# CircuitDiagram.net
KiCad netlist of a schematic drawn in EAGLE
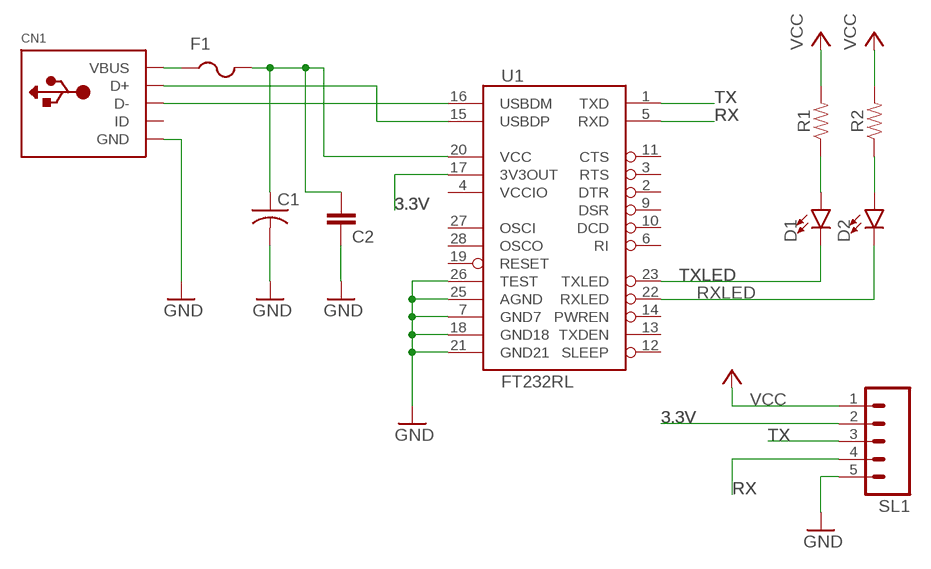
[diagram p0: schematic, sheet 1]

(export (version "E")
  (design (tool "Eeschema 10.0.6"))
  (components
    (comp (ref "C1")
      (value "C-USC1206")
      (footprint "eagle-import:C1206")
      (libsource (lib "eagle-import") (part "C-USC1206"))
    )
    (comp (ref "C2")
      (value "1.0uF")
      (footprint "eagle-import:1206")
      (libsource (lib "eagle-import") (part "1.0UF-1206-50V-10%"))
    )
    (comp (ref "CN1")
      (value "USBMINIB")
      (footprint "eagle-import:USB-MINIB")
      (libsource (lib "eagle-import") (part "USBMINIB"))
    )
    (comp (ref "D1")
      (value "LED1206")
      (footprint "eagle-import:LED-1206")
      (libsource (lib "eagle-import") (part "LED1206"))
    )
    (comp (ref "D2")
      (value "LED1206")
      (footprint "eagle-import:LED-1206")
      (libsource (lib "eagle-import") (part "LED1206"))
    )
    (comp (ref "F1")
      (value "PTCFUSE-1206")
      (footprint "eagle-import:R1206")
      (libsource (lib "eagle-import") (part "PTCFUSE-1206"))
    )
    (comp (ref "R1")
      (value "RESISTOR1206")
      (footprint "eagle-import:1206")
      (libsource (lib "eagle-import") (part "RESISTOR1206"))
    )
    (comp (ref "R2")
      (value "RESISTOR1206")
      (footprint "eagle-import:1206")
      (libsource (lib "eagle-import") (part "RESISTOR1206"))
    )
    (comp (ref "SL1")
      (value "M05")
      (footprint "eagle-import:05P")
      (libsource (lib "eagle-import") (part "M05"))
    )
    (comp (ref "U1")
      (value "FT232RL")
      (footprint "eagle-import:SSOP28DB")
      (libsource (lib "eagle-import") (part "FT232RLSSOP"))
    )
  )
  (nets
    (net (code "1") (name "/3.3V") (class "Default")
      (node (ref "SL1") (pin "2") (pinfunction "2_2") (pintype "passive"))
      (node (ref "U1") (pin "17") (pinfunction "3V3OUT_17") (pintype "output"))
    )
    (net (code "2") (name "/RX") (class "Default")
      (node (ref "SL1") (pin "4") (pinfunction "4_4") (pintype "passive"))
      (node (ref "U1") (pin "5") (pinfunction "RXD_5") (pintype "input"))
    )
    (net (code "3") (name "/RXLED") (class "Default")
      (node (ref "D2") (pin "C") (pinfunction "C_C") (pintype "passive"))
      (node (ref "U1") (pin "22") (pinfunction "RXLED_22") (pintype "input"))
    )
    (net (code "4") (name "/TX") (class "Default")
      (node (ref "SL1") (pin "3") (pinfunction "3_3") (pintype "passive"))
      (node (ref "U1") (pin "1") (pinfunction "TXD_1") (pintype "output"))
    )
    (net (code "5") (name "/TXLED") (class "Default")
      (node (ref "D1") (pin "C") (pinfunction "C_C") (pintype "passive"))
      (node (ref "U1") (pin "23") (pinfunction "TXLED_23") (pintype "input"))
    )
    (net (code "6") (name "/VCCIO") (class "Default")
      (node (ref "U1") (pin "4") (pinfunction "VCCIO_4") (pintype "power_in"))
    )
    (net (code "7") (name "GND") (class "Default")
      (node (ref "C1") (pin "2") (pinfunction "2_2") (pintype "passive"))
      (node (ref "C2") (pin "2") (pinfunction "2_2") (pintype "passive"))
      (node (ref "CN1") (pin "GND") (pinfunction "GND_GND") (pintype "power_in"))
      (node (ref "SL1") (pin "5") (pinfunction "5_5") (pintype "passive"))
      (node (ref "U1") (pin "18") (pinfunction "GND18_18") (pintype "power_in"))
      (node (ref "U1") (pin "21") (pinfunction "GND21_21") (pintype "power_in"))
      (node (ref "U1") (pin "25") (pinfunction "AGND_25") (pintype "power_in"))
      (node (ref "U1") (pin "26") (pinfunction "TEST_26") (pintype "input"))
      (node (ref "U1") (pin "7") (pinfunction "GND7_7") (pintype "power_in"))
    )
    (net (code "8") (name "Net-(CN1-PadVBUS)") (class "Default")
      (node (ref "CN1") (pin "VBUS") (pinfunction "VBUS_VBUS") (pintype "power_in"))
      (node (ref "F1") (pin "1") (pinfunction "1_1") (pintype "passive"))
    )
    (net (code "9") (name "Net-(D1-PadA)") (class "Default")
      (node (ref "D1") (pin "A") (pinfunction "A_A") (pintype "passive"))
      (node (ref "R1") (pin "1") (pinfunction "1_1") (pintype "passive"))
    )
    (net (code "10") (name "Net-(D2-PadA)") (class "Default")
      (node (ref "D2") (pin "A") (pinfunction "A_A") (pintype "passive"))
      (node (ref "R2") (pin "1") (pinfunction "1_1") (pintype "passive"))
    )
    (net (code "11") (name "Net-(U1-USBDM)") (class "Default")
      (node (ref "CN1") (pin "D-") (pinfunction "D-_D-") (pintype "bidirectional"))
      (node (ref "U1") (pin "16") (pinfunction "USBDM_16") (pintype "bidirectional"))
    )
    (net (code "12") (name "Net-(U1-USBDP)") (class "Default")
      (node (ref "CN1") (pin "D+") (pinfunction "D+_D+") (pintype "bidirectional"))
      (node (ref "U1") (pin "15") (pinfunction "USBDP_15") (pintype "bidirectional"))
    )
    (net (code "13") (name "Net-(U1-VCC)") (class "Default")
      (node (ref "C1") (pin "1") (pinfunction "1_1") (pintype "passive"))
      (node (ref "C2") (pin "1") (pinfunction "1_1") (pintype "passive"))
      (node (ref "F1") (pin "2") (pinfunction "2_2") (pintype "passive"))
      (node (ref "U1") (pin "20") (pinfunction "VCC_20") (pintype "power_in"))
    )
    (net (code "14") (name "VCC") (class "Default")
      (node (ref "R1") (pin "2") (pinfunction "2_2") (pintype "passive"))
      (node (ref "R2") (pin "2") (pinfunction "2_2") (pintype "passive"))
      (node (ref "SL1") (pin "1") (pinfunction "1_1") (pintype "passive"))
    )
    (net (code "15") (name "unconnected-(CN1-PadID)") (class "Default")
      (node (ref "CN1") (pin "ID") (pinfunction "ID_ID") (pintype "bidirectional"))
    )
    (net (code "16") (name "unconnected-(U1-CTS-Pad11)") (class "Default")
      (node (ref "U1") (pin "11") (pinfunction "CTS_11") (pintype "input"))
    )
    (net (code "17") (name "unconnected-(U1-DCD-Pad10)") (class "Default")
      (node (ref "U1") (pin "10") (pinfunction "DCD_10") (pintype "input"))
    )
    (net (code "18") (name "unconnected-(U1-DSR-Pad9)") (class "Default")
      (node (ref "U1") (pin "9") (pinfunction "DSR_9") (pintype "input"))
    )
    (net (code "19") (name "unconnected-(U1-DTR-Pad2)") (class "Default")
      (node (ref "U1") (pin "2") (pinfunction "DTR_2") (pintype "output"))
    )
    (net (code "20") (name "unconnected-(U1-OSCI-Pad27)") (class "Default")
      (node (ref "U1") (pin "27") (pinfunction "OSCI_27") (pintype "input"))
    )
    (net (code "21") (name "unconnected-(U1-OSCO-Pad28)") (class "Default")
      (node (ref "U1") (pin "28") (pinfunction "OSCO_28") (pintype "output"))
    )
    (net (code "22") (name "unconnected-(U1-PWREN-Pad14)") (class "Default")
      (node (ref "U1") (pin "14") (pinfunction "PWREN_14") (pintype "input"))
    )
    (net (code "23") (name "unconnected-(U1-RESET-Pad19)") (class "Default")
      (node (ref "U1") (pin "19") (pinfunction "RESET_19") (pintype "input"))
    )
    (net (code "24") (name "unconnected-(U1-RI-Pad6)") (class "Default")
      (node (ref "U1") (pin "6") (pinfunction "RI_6") (pintype "input"))
    )
    (net (code "25") (name "unconnected-(U1-RTS-Pad3)") (class "Default")
      (node (ref "U1") (pin "3") (pinfunction "RTS_3") (pintype "output"))
    )
    (net (code "26") (name "unconnected-(U1-SLEEP-Pad12)") (class "Default")
      (node (ref "U1") (pin "12") (pinfunction "SLEEP_12") (pintype "input"))
    )
    (net (code "27") (name "unconnected-(U1-TXDEN-Pad13)") (class "Default")
      (node (ref "U1") (pin "13") (pinfunction "TXDEN_13") (pintype "input"))
    )
  )
)
